# MS20_schematic.net
KiCad netlist of a schematic drawn in Altium Designer
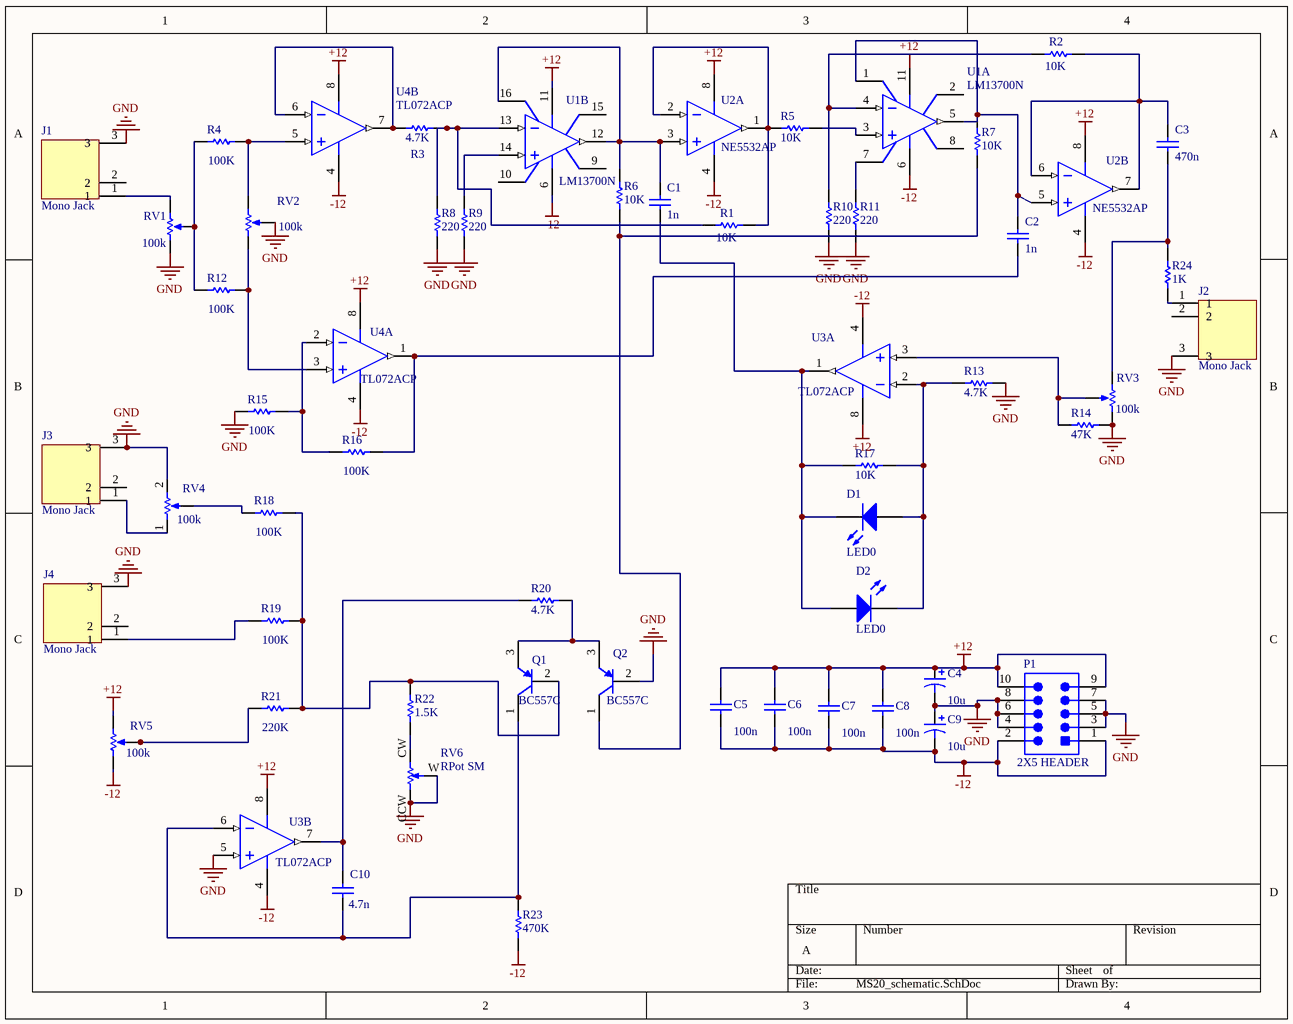
[diagram p0: MS20_schematic.SchDoc]

(export (version "E")
  (design (tool "Eeschema 10.0.6"))
  (components
    (comp (ref "C1")
      (value "1n")
      (footprint "RAD-0.3")
      (description "Capacitor")
      (fields (field (name "Comment") "Cap") (field (name "PUBLISHER") "Altium Limited"))
      (libsource (lib "Miscellaneous Devices") (part "Cap"))
    )
    (comp (ref "C2")
      (value "1n")
      (footprint "RAD-0.3")
      (description "Capacitor")
      (fields (field (name "Comment") "Cap") (field (name "PUBLISHER") "Altium Limited"))
      (libsource (lib "Miscellaneous Devices") (part "Cap"))
    )
    (comp (ref "C3")
      (value "470n")
      (footprint "RAD-0.3")
      (description "Capacitor")
      (fields (field (name "Comment") "Cap") (field (name "PUBLISHER") "Altium Limited"))
      (libsource (lib "Miscellaneous Devices") (part "Cap"))
    )
    (comp (ref "C4")
      (value "10u")
      (footprint "RB7.6-15")
      (description "Polarized Capacitor (Radial)")
      (fields (field (name "Comment") "Cap Pol1") (field (name "PUBLISHER") "Altium Limited"))
      (libsource (lib "Miscellaneous Devices") (part "Cap Pol1"))
    )
    (comp (ref "C5")
      (value "100n")
      (footprint "RAD-0.3")
      (description "Capacitor")
      (fields (field (name "Comment") "Cap") (field (name "PUBLISHER") "Altium Limited"))
      (libsource (lib "Miscellaneous Devices") (part "Cap"))
    )
    (comp (ref "C6")
      (value "100n")
      (footprint "RAD-0.3")
      (description "Capacitor")
      (fields (field (name "Comment") "Cap") (field (name "PUBLISHER") "Altium Limited"))
      (libsource (lib "Miscellaneous Devices") (part "Cap"))
    )
    (comp (ref "C7")
      (value "100n")
      (footprint "RAD-0.3")
      (description "Capacitor")
      (fields (field (name "Comment") "Cap") (field (name "PUBLISHER") "Altium Limited"))
      (libsource (lib "Miscellaneous Devices") (part "Cap"))
    )
    (comp (ref "C8")
      (value "100n")
      (footprint "RAD-0.3")
      (description "Capacitor")
      (fields (field (name "Comment") "Cap") (field (name "PUBLISHER") "Altium Limited"))
      (libsource (lib "Miscellaneous Devices") (part "Cap"))
    )
    (comp (ref "C9")
      (value "10u")
      (footprint "RB7.6-15")
      (description "Polarized Capacitor (Radial)")
      (fields (field (name "Comment") "Cap Pol1") (field (name "PUBLISHER") "Altium Limited"))
      (libsource (lib "Miscellaneous Devices") (part "Cap Pol1"))
    )
    (comp (ref "C10")
      (value "4.7n")
      (footprint "RAD-0.3")
      (description "Capacitor")
      (fields (field (name "Comment") "Cap") (field (name "PUBLISHER") "Altium Limited"))
      (libsource (lib "Miscellaneous Devices") (part "Cap"))
    )
    (comp (ref "D1")
      (value "LED0")
      (footprint "LED-0")
      (description "Typical INFRARED GaAs LED")
      (fields (field (name "PUBLISHER") "Altium Limited"))
      (libsource (lib "Miscellaneous Devices") (part "LED0"))
    )
    (comp (ref "D2")
      (value "LED0")
      (footprint "LED-0")
      (description "Typical INFRARED GaAs LED")
      (fields (field (name "PUBLISHER") "Altium Limited"))
      (libsource (lib "Miscellaneous Devices") (part "LED0"))
    )
    (comp (ref "J1")
      (value "Mono Jack")
      (footprint "MONO_Jack")
      (description "Phone Connectors Audio Socket 3.5MM 2P SCR")
      (fields (field (name "MANUFACTURER") "Schurter") (field (name "MANUFACTURER PART NUMBER") "4832.2211"))
      (libsource (lib "") (part "4832.2211_1"))
    )
    (comp (ref "J2")
      (value "Mono Jack")
      (footprint "MONO_Jack")
      (description "Phone Connectors Audio Socket 3.5MM 2P SCR")
      (fields (field (name "MANUFACTURER") "Schurter") (field (name "MANUFACTURER PART NUMBER") "4832.2211"))
      (libsource (lib "Schlib1") (part "4832.2211"))
    )
    (comp (ref "J3")
      (value "Mono Jack")
      (footprint "MONO_Jack")
      (description "Phone Connectors Audio Socket 3.5MM 2P SCR")
      (fields (field (name "MANUFACTURER") "Schurter") (field (name "MANUFACTURER PART NUMBER") "4832.2211"))
      (libsource (lib "") (part "4832.2211_1"))
    )
    (comp (ref "J4")
      (value "Mono Jack")
      (footprint "MONO_Jack")
      (description "Phone Connectors Audio Socket 3.5MM 2P SCR")
      (fields (field (name "MANUFACTURER") "Schurter") (field (name "MANUFACTURER PART NUMBER") "4832.2211"))
      (libsource (lib "") (part "4832.2211_1"))
    )
    (comp (ref "P1")
      (value "2X5 HEADER")
      (footprint "TECO-1-1634688-0-10_V")
      (fields (field (name "MANUFACTURER") "TE Connectivity") (field (name "PARTNUMBER") "1-1634688-0"))
      (libsource (lib "Altium Content Vault") (part "CN-2P-M-R10"))
    )
    (comp (ref "Q1")
      (value "BC557C")
      (footprint "ONSC-TO-92-3-29-11")
      (description "Amplifier Transistor, PNP Silicon, 3-Pin TO-92, Bulk Box")
      (fields (field (name "MANUFACTURER") "On Semiconductor"))
      (libsource (lib "Altium Content Vault") (part "ONSC-PNP-C1B2E3-3"))
    )
    (comp (ref "Q2")
      (value "BC557C")
      (footprint "ONSC-TO-92-3-29-11")
      (description "Amplifier Transistor, PNP Silicon, 3-Pin TO-92, Bulk Box")
      (fields (field (name "MANUFACTURER") "On Semiconductor"))
      (libsource (lib "Altium Content Vault") (part "ONSC-PNP-C1B2E3-3"))
    )
    (comp (ref "R1")
      (value "10K")
      (footprint "AXIAL-0.3")
      (description "Resistor")
      (fields (field (name "Comment") "Res1") (field (name "PUBLISHER") "Altium Limited"))
      (libsource (lib "Miscellaneous Devices") (part "Res1"))
    )
    (comp (ref "R2")
      (value "10K")
      (footprint "AXIAL-0.3")
      (description "Resistor")
      (fields (field (name "Comment") "Res1") (field (name "PUBLISHER") "Altium Limited"))
      (libsource (lib "Miscellaneous Devices") (part "Res1"))
    )
    (comp (ref "R3")
      (value "4.7K")
      (footprint "AXIAL-0.3")
      (description "Resistor")
      (fields (field (name "Comment") "Res1") (field (name "PUBLISHER") "Altium Limited"))
      (libsource (lib "Miscellaneous Devices") (part "Res1"))
    )
    (comp (ref "R4")
      (value "100K")
      (footprint "AXIAL-0.3")
      (description "Resistor")
      (fields (field (name "Comment") "Res1") (field (name "PUBLISHER") "Altium Limited"))
      (libsource (lib "Miscellaneous Devices") (part "Res1"))
    )
    (comp (ref "R5")
      (value "10K")
      (footprint "AXIAL-0.3")
      (description "Resistor")
      (fields (field (name "Comment") "Res1") (field (name "PUBLISHER") "Altium Limited"))
      (libsource (lib "Miscellaneous Devices") (part "Res1"))
    )
    (comp (ref "R6")
      (value "10K")
      (footprint "AXIAL-0.3")
      (description "Resistor")
      (fields (field (name "Comment") "Res1") (field (name "PUBLISHER") "Altium Limited"))
      (libsource (lib "Miscellaneous Devices") (part "Res1"))
    )
    (comp (ref "R7")
      (value "10K")
      (footprint "AXIAL-0.3")
      (description "Resistor")
      (fields (field (name "Comment") "Res1") (field (name "PUBLISHER") "Altium Limited"))
      (libsource (lib "Miscellaneous Devices") (part "Res1"))
    )
    (comp (ref "R8")
      (value "220")
      (footprint "AXIAL-0.3")
      (description "Resistor")
      (fields (field (name "Comment") "Res1") (field (name "PUBLISHER") "Altium Limited"))
      (libsource (lib "Miscellaneous Devices") (part "Res1"))
    )
    (comp (ref "R9")
      (value "220")
      (footprint "AXIAL-0.3")
      (description "Resistor")
      (fields (field (name "Comment") "Res1") (field (name "PUBLISHER") "Altium Limited"))
      (libsource (lib "Miscellaneous Devices") (part "Res1"))
    )
    (comp (ref "R10")
      (value "220")
      (footprint "AXIAL-0.3")
      (description "Resistor")
      (fields (field (name "Comment") "Res1") (field (name "PUBLISHER") "Altium Limited"))
      (libsource (lib "Miscellaneous Devices") (part "Res1"))
    )
    (comp (ref "R11")
      (value "220")
      (footprint "AXIAL-0.3")
      (description "Resistor")
      (fields (field (name "Comment") "Res1") (field (name "PUBLISHER") "Altium Limited"))
      (libsource (lib "Miscellaneous Devices") (part "Res1"))
    )
    (comp (ref "R12")
      (value "100K")
      (footprint "AXIAL-0.3")
      (description "Resistor")
      (fields (field (name "Comment") "Res1") (field (name "PUBLISHER") "Altium Limited"))
      (libsource (lib "Miscellaneous Devices") (part "Res1"))
    )
    (comp (ref "R13")
      (value "4.7K")
      (footprint "AXIAL-0.3")
      (description "Resistor")
      (fields (field (name "Comment") "Res1") (field (name "PUBLISHER") "Altium Limited"))
      (libsource (lib "Miscellaneous Devices") (part "Res1"))
    )
    (comp (ref "R14")
      (value "47K")
      (footprint "AXIAL-0.3")
      (description "Resistor")
      (fields (field (name "Comment") "Res1") (field (name "PUBLISHER") "Altium Limited"))
      (libsource (lib "Miscellaneous Devices") (part "Res1"))
    )
    (comp (ref "R15")
      (value "100K")
      (footprint "AXIAL-0.3")
      (description "Resistor")
      (fields (field (name "Comment") "Res1") (field (name "PUBLISHER") "Altium Limited"))
      (libsource (lib "Miscellaneous Devices") (part "Res1"))
    )
    (comp (ref "R16")
      (value "100K")
      (footprint "AXIAL-0.3")
      (description "Resistor")
      (fields (field (name "Comment") "Res1") (field (name "PUBLISHER") "Altium Limited"))
      (libsource (lib "Miscellaneous Devices") (part "Res1"))
    )
    (comp (ref "R17")
      (value "10K")
      (footprint "AXIAL-0.3")
      (description "Resistor")
      (fields (field (name "Comment") "Res1") (field (name "PUBLISHER") "Altium Limited"))
      (libsource (lib "Miscellaneous Devices") (part "Res1"))
    )
    (comp (ref "R18")
      (value "100K")
      (footprint "AXIAL-0.3")
      (description "Resistor")
      (fields (field (name "Comment") "Res1") (field (name "PUBLISHER") "Altium Limited"))
      (libsource (lib "Miscellaneous Devices") (part "Res1"))
    )
    (comp (ref "R19")
      (value "100K")
      (footprint "AXIAL-0.3")
      (description "Resistor")
      (fields (field (name "Comment") "Res1") (field (name "PUBLISHER") "Altium Limited"))
      (libsource (lib "Miscellaneous Devices") (part "Res1"))
    )
    (comp (ref "R20")
      (value "4.7K")
      (footprint "AXIAL-0.3")
      (description "Resistor")
      (fields (field (name "Comment") "Res1") (field (name "PUBLISHER") "Altium Limited"))
      (libsource (lib "Miscellaneous Devices") (part "Res1"))
    )
    (comp (ref "R21")
      (value "220K")
      (footprint "AXIAL-0.3")
      (description "Resistor")
      (fields (field (name "Comment") "Res1") (field (name "PUBLISHER") "Altium Limited"))
      (libsource (lib "Miscellaneous Devices") (part "Res1"))
    )
    (comp (ref "R22")
      (value "1.5K")
      (footprint "AXIAL-0.3")
      (description "Resistor")
      (fields (field (name "Comment") "Res1") (field (name "PUBLISHER") "Altium Limited"))
      (libsource (lib "Miscellaneous Devices") (part "Res1"))
    )
    (comp (ref "R23")
      (value "470K")
      (footprint "AXIAL-0.3")
      (description "Resistor")
      (fields (field (name "Comment") "Res1") (field (name "PUBLISHER") "Altium Limited"))
      (libsource (lib "Miscellaneous Devices") (part "Res1"))
    )
    (comp (ref "R24")
      (value "1K")
      (footprint "AXIAL-0.3")
      (description "Resistor")
      (fields (field (name "Comment") "Res1") (field (name "PUBLISHER") "Altium Limited"))
      (libsource (lib "Miscellaneous Devices") (part "Res1"))
    )
    (comp (ref "RV1")
      (value "100k")
      (footprint "VR5")
      (description "Potentiometer")
      (fields (field (name "Comment") "RPot") (field (name "PUBLISHER") "Altium Limited"))
      (libsource (lib "Miscellaneous Devices") (part "RPot"))
    )
    (comp (ref "RV2")
      (value "100k")
      (footprint "VR5")
      (description "Potentiometer")
      (fields (field (name "Comment") "RPot") (field (name "PUBLISHER") "Altium Limited"))
      (libsource (lib "Miscellaneous Devices") (part "RPot"))
    )
    (comp (ref "RV3")
      (value "100k")
      (footprint "VR5")
      (description "Potentiometer")
      (fields (field (name "Comment") "RPot") (field (name "PUBLISHER") "Altium Limited"))
      (libsource (lib "Miscellaneous Devices") (part "RPot"))
    )
    (comp (ref "RV4")
      (value "100k")
      (footprint "VR5")
      (description "Potentiometer")
      (fields (field (name "Comment") "RPot") (field (name "PUBLISHER") "Altium Limited"))
      (libsource (lib "") (part "RPot_1"))
    )
    (comp (ref "RV5")
      (value "100k")
      (footprint "VR5")
      (description "Potentiometer")
      (fields (field (name "Comment") "RPot") (field (name "PUBLISHER") "Altium Limited"))
      (libsource (lib "Miscellaneous Devices") (part "RPot"))
    )
    (comp (ref "RV6")
      (value "RPot SM")
      (footprint "POT4MM-2")
      (description "Square Trimming Potentiometer")
      (fields (field (name "PUBLISHER") "Altium Limited"))
      (libsource (lib "Miscellaneous Devices") (part "RPot SM"))
    )
    (comp (ref "U1")
      (value "LM13700N")
      (footprint "NFG0016A")
      (description "Dual Operational Transconductance Amplifier with Linearizing Diodes and Buffers, 16-pin MDIP")
      (fields (field (name "MANUFACTURER") "Texas Instruments"))
      (libsource (lib "Altium Content Vault") (part "AMP-TRCA-LM13700-16"))
    )
    (comp (ref "U2")
      (value "NE5532AP")
      (footprint "P0008A")
      (description "Dual Low-Noise Operational Amplifier, 10 to 30 V, 0 to 70 degC, 8-pin DIP (P8), Pb-Free (RoHS)")
      (fields (field (name "MANUFACTURER") "Texas Instruments"))
      (libsource (lib "Altium Content Vault") (part "TI-AMP-D6-2-8_D"))
    )
    (comp (ref "U3")
      (value "TL072ACP")
      (footprint "P0008A")
      (fields (field (name "MANUFACTURER") "Texas Instruments"))
      (libsource (lib "Altium Content Vault") (part "TI-AMP-D6-2-8_D"))
    )
    (comp (ref "U4")
      (value "TL072ACP")
      (footprint "P0008A")
      (fields (field (name "MANUFACTURER") "Texas Instruments"))
      (libsource (lib "Altium Content Vault") (part "TI-AMP-D6-2-8_D"))
    )
  )
  (nets
    (net (code "1") (name "+12") (class "Default")
      (node (ref "C4") (pin "1") (pinfunction "1_1") (pintype "passive"))
      (node (ref "C5") (pin "1") (pinfunction "1_1") (pintype "passive"))
      (node (ref "C6") (pin "1") (pinfunction "1_1") (pintype "passive"))
      (node (ref "C7") (pin "1") (pinfunction "1_1") (pintype "passive"))
      (node (ref "C8") (pin "1") (pinfunction "1_1") (pintype "passive"))
      (node (ref "P1") (pin "10") (pinfunction "10_10") (pintype "passive"))
      (node (ref "P1") (pin "9") (pinfunction "9_9") (pintype "passive"))
      (node (ref "RV5") (pin "2") (pinfunction "BOT_2") (pintype "passive"))
      (node (ref "U1") (pin "11") (pinfunction "V+_11") (pintype "power_in"))
      (node (ref "U2") (pin "8") (pinfunction "VCC+_8") (pintype "power_in"))
      (node (ref "U3") (pin "8") (pinfunction "VCC+_8") (pintype "power_in"))
      (node (ref "U4") (pin "8") (pinfunction "VCC+_8") (pintype "power_in"))
    )
    (net (code "2") (name "-12") (class "Default")
      (node (ref "C5") (pin "2") (pinfunction "2_2") (pintype "passive"))
      (node (ref "C6") (pin "2") (pinfunction "2_2") (pintype "passive"))
      (node (ref "C7") (pin "2") (pinfunction "2_2") (pintype "passive"))
      (node (ref "C8") (pin "2") (pinfunction "2_2") (pintype "passive"))
      (node (ref "C9") (pin "2") (pinfunction "2_2") (pintype "passive"))
      (node (ref "P1") (pin "1") (pinfunction "1_1") (pintype "passive"))
      (node (ref "P1") (pin "2") (pinfunction "2_2") (pintype "passive"))
      (node (ref "R23") (pin "2") (pinfunction "2_2") (pintype "passive"))
      (node (ref "RV5") (pin "1") (pinfunction "TOP_1") (pintype "passive"))
      (node (ref "U1") (pin "6") (pinfunction "V-_6") (pintype "power_in"))
      (node (ref "U2") (pin "4") (pinfunction "VCC-_4") (pintype "power_in"))
      (node (ref "U3") (pin "4") (pinfunction "VCC-_4") (pintype "power_in"))
      (node (ref "U4") (pin "4") (pinfunction "VCC-_4") (pintype "power_in"))
    )
    (net (code "3") (name "GND") (class "Default")
      (node (ref "C4") (pin "2") (pinfunction "2_2") (pintype "passive"))
      (node (ref "C9") (pin "1") (pinfunction "1_1") (pintype "passive"))
      (node (ref "J1") (pin "3") (pinfunction "3_3") (pintype "passive"))
      (node (ref "J2") (pin "3") (pinfunction "3_3") (pintype "passive"))
      (node (ref "J3") (pin "3") (pinfunction "3_3") (pintype "passive"))
      (node (ref "J4") (pin "3") (pinfunction "3_3") (pintype "passive"))
      (node (ref "P1") (pin "3") (pinfunction "3_3") (pintype "passive"))
      (node (ref "P1") (pin "4") (pinfunction "4_4") (pintype "passive"))
      (node (ref "P1") (pin "5") (pinfunction "5_5") (pintype "passive"))
      (node (ref "P1") (pin "6") (pinfunction "6_6") (pintype "passive"))
      (node (ref "P1") (pin "7") (pinfunction "7_7") (pintype "passive"))
      (node (ref "P1") (pin "8") (pinfunction "8_8") (pintype "passive"))
      (node (ref "Q2") (pin "2") (pinfunction "B_2") (pintype "passive"))
      (node (ref "R10") (pin "1") (pinfunction "1_1") (pintype "passive"))
      (node (ref "R11") (pin "1") (pinfunction "1_1") (pintype "passive"))
      (node (ref "R13") (pin "1") (pinfunction "1_1") (pintype "passive"))
      (node (ref "R14") (pin "1") (pinfunction "1_1") (pintype "passive"))
      (node (ref "R15") (pin "1") (pinfunction "1_1") (pintype "passive"))
      (node (ref "R8") (pin "1") (pinfunction "1_1") (pintype "passive"))
      (node (ref "R9") (pin "1") (pinfunction "1_1") (pintype "passive"))
      (node (ref "RV1") (pin "1") (pinfunction "TOP_1") (pintype "passive"))
      (node (ref "RV2") (pin "3") (pinfunction "TAP_3") (pintype "passive"))
      (node (ref "RV3") (pin "2") (pinfunction "BOT_2") (pintype "passive"))
      (node (ref "RV4") (pin "2") (pinfunction "BOT_2") (pintype "passive"))
      (node (ref "RV6") (pin "CCW") (pinfunction "-_CCW") (pintype "passive"))
      (node (ref "RV6") (pin "W") (pinfunction "W_W") (pintype "passive"))
      (node (ref "U3") (pin "5") (pinfunction "IN2+_5") (pintype "input"))
    )
    (net (code "4") (name "Net-(D1-A)") (class "Default")
      (node (ref "D1") (pin "1") (pinfunction "A_1") (pintype "passive"))
      (node (ref "D2") (pin "2") (pinfunction "K_2") (pintype "passive"))
      (node (ref "R13") (pin "2") (pinfunction "2_2") (pintype "passive"))
      (node (ref "R17") (pin "1") (pinfunction "1_1") (pintype "passive"))
      (node (ref "U3") (pin "2") (pinfunction "IN1-_2") (pintype "input"))
    )
    (net (code "5") (name "Net-(D1-K)") (class "Default")
      (node (ref "C1") (pin "2") (pinfunction "2_2") (pintype "passive"))
      (node (ref "D1") (pin "2") (pinfunction "K_2") (pintype "passive"))
      (node (ref "D2") (pin "1") (pinfunction "A_1") (pintype "passive"))
      (node (ref "R17") (pin "2") (pinfunction "2_2") (pintype "passive"))
      (node (ref "U3") (pin "1") (pinfunction "OUT1_1") (pintype "output"))
    )
    (net (code "6") (name "Net-(J2-Pad1)") (class "Default")
      (node (ref "J2") (pin "1") (pinfunction "1_1") (pintype "passive"))
      (node (ref "R24") (pin "1") (pinfunction "1_1") (pintype "passive"))
    )
    (net (code "7") (name "Net-(J4-Pad1)") (class "Default")
      (node (ref "J4") (pin "1") (pinfunction "1_1") (pintype "passive"))
      (node (ref "R19") (pin "1") (pinfunction "1_1") (pintype "passive"))
    )
    (net (code "8") (name "Net-(Q1-B)") (class "Default")
      (node (ref "Q1") (pin "2") (pinfunction "B_2") (pintype "passive"))
      (node (ref "R18") (pin "2") (pinfunction "2_2") (pintype "passive"))
      (node (ref "R19") (pin "2") (pinfunction "2_2") (pintype "passive"))
      (node (ref "R21") (pin "2") (pinfunction "2_2") (pintype "passive"))
      (node (ref "R22") (pin "2") (pinfunction "2_2") (pintype "passive"))
    )
    (net (code "9") (name "Net-(Q1-C)") (class "Default")
      (node (ref "C10") (pin "2") (pinfunction "2_2") (pintype "passive"))
      (node (ref "Q1") (pin "1") (pinfunction "C_1") (pintype "passive"))
      (node (ref "R23") (pin "1") (pinfunction "1_1") (pintype "passive"))
      (node (ref "U3") (pin "6") (pinfunction "IN2-_6") (pintype "input"))
    )
    (net (code "10") (name "Net-(Q1-E)") (class "Default")
      (node (ref "Q1") (pin "3") (pinfunction "E_3") (pintype "passive"))
      (node (ref "Q2") (pin "3") (pinfunction "E_3") (pintype "passive"))
      (node (ref "R20") (pin "1") (pinfunction "1_1") (pintype "passive"))
    )
    (net (code "11") (name "Net-(Q2-C)") (class "Default")
      (node (ref "Q2") (pin "1") (pinfunction "C_1") (pintype "passive"))
      (node (ref "R6") (pin "1") (pinfunction "1_1") (pintype "passive"))
      (node (ref "R7") (pin "1") (pinfunction "1_1") (pintype "passive"))
    )
    (net (code "12") (name "Net-(RV1-BOT)") (class "Default")
      (node (ref "J1") (pin "1") (pinfunction "1_1") (pintype "passive"))
      (node (ref "RV1") (pin "2") (pinfunction "BOT_2") (pintype "passive"))
    )
    (net (code "13") (name "Net-(RV1-TAP)") (class "Default")
      (node (ref "R12") (pin "1") (pinfunction "1_1") (pintype "passive"))
      (node (ref "R4") (pin "1") (pinfunction "1_1") (pintype "passive"))
      (node (ref "RV1") (pin "3") (pinfunction "TAP_3") (pintype "passive"))
    )
    (net (code "14") (name "Net-(RV2-BOT)") (class "Default")
      (node (ref "R4") (pin "2") (pinfunction "2_2") (pintype "passive"))
      (node (ref "RV2") (pin "2") (pinfunction "BOT_2") (pintype "passive"))
      (node (ref "U4") (pin "5") (pinfunction "IN2+_5") (pintype "input"))
    )
    (net (code "15") (name "Net-(RV2-TOP)") (class "Default")
      (node (ref "R12") (pin "2") (pinfunction "2_2") (pintype "passive"))
      (node (ref "RV2") (pin "1") (pinfunction "TOP_1") (pintype "passive"))
      (node (ref "U4") (pin "3") (pinfunction "IN1+_3") (pintype "input"))
    )
    (net (code "16") (name "Net-(RV3-TAP)") (class "Default")
      (node (ref "R14") (pin "2") (pinfunction "2_2") (pintype "passive"))
      (node (ref "RV3") (pin "3") (pinfunction "TAP_3") (pintype "passive"))
      (node (ref "U3") (pin "3") (pinfunction "IN1+_3") (pintype "input"))
    )
    (net (code "17") (name "Net-(RV3-TOP)") (class "Default")
      (node (ref "C3") (pin "2") (pinfunction "2_2") (pintype "passive"))
      (node (ref "R24") (pin "2") (pinfunction "2_2") (pintype "passive"))
      (node (ref "RV3") (pin "1") (pinfunction "TOP_1") (pintype "passive"))
    )
    (net (code "18") (name "Net-(RV4-TAP)") (class "Default")
      (node (ref "R18") (pin "1") (pinfunction "1_1") (pintype "passive"))
      (node (ref "RV4") (pin "3") (pinfunction "TAP_3") (pintype "passive"))
    )
    (net (code "19") (name "Net-(RV4-TOP)") (class "Default")
      (node (ref "J3") (pin "1") (pinfunction "1_1") (pintype "passive"))
      (node (ref "RV4") (pin "1") (pinfunction "TOP_1") (pintype "passive"))
    )
    (net (code "20") (name "Net-(RV5-TAP)") (class "Default")
      (node (ref "R21") (pin "1") (pinfunction "1_1") (pintype "passive"))
      (node (ref "RV5") (pin "3") (pinfunction "TAP_3") (pintype "passive"))
    )
    (net (code "21") (name "Net-(RV6-+)") (class "Default")
      (node (ref "R22") (pin "1") (pinfunction "1_1") (pintype "passive"))
      (node (ref "RV6") (pin "CW") (pinfunction "+_CW") (pintype "passive"))
    )
    (net (code "22") (name "Net-(U1A-AMP_BIAS_IN1)") (class "Default")
      (node (ref "C2") (pin "1") (pinfunction "1_1") (pintype "passive"))
      (node (ref "R7") (pin "2") (pinfunction "2_2") (pintype "passive"))
      (node (ref "U1") (pin "1") (pinfunction "AMP_BIAS_IN1_1") (pintype "passive"))
      (node (ref "U1") (pin "5") (pinfunction "OUT1_5") (pintype "output"))
      (node (ref "U2") (pin "5") (pinfunction "IN2+_5") (pintype "input"))
    )
    (net (code "23") (name "Net-(U1A-BUF_IN1)") (class "Default")
      (node (ref "R11") (pin "2") (pinfunction "2_2") (pintype "passive"))
      (node (ref "U1") (pin "7") (pinfunction "BUF_IN1_7") (pintype "passive"))
    )
    (net (code "24") (name "Net-(U1A-IN1+)") (class "Default")
      (node (ref "R5") (pin "1") (pinfunction "1_1") (pintype "passive"))
      (node (ref "U1") (pin "3") (pinfunction "IN1+_3") (pintype "input"))
    )
    (net (code "25") (name "Net-(U1A-IN1-)") (class "Default")
      (node (ref "R10") (pin "2") (pinfunction "2_2") (pintype "passive"))
      (node (ref "R2") (pin "2") (pinfunction "2_2") (pintype "passive"))
      (node (ref "U1") (pin "4") (pinfunction "IN1-_4") (pintype "input"))
    )
    (net (code "26") (name "Net-(U1B-AMP_BIAS_IN2)") (class "Default")
      (node (ref "C1") (pin "1") (pinfunction "1_1") (pintype "passive"))
      (node (ref "R6") (pin "2") (pinfunction "2_2") (pintype "passive"))
      (node (ref "U1") (pin "12") (pinfunction "OUT2_12") (pintype "output"))
      (node (ref "U1") (pin "16") (pinfunction "AMP_BIAS_IN2_16") (pintype "passive"))
      (node (ref "U2") (pin "3") (pinfunction "IN1+_3") (pintype "input"))
    )
    (net (code "27") (name "Net-(U1B-IN2+)") (class "Default")
      (node (ref "R9") (pin "2") (pinfunction "2_2") (pintype "passive"))
      (node (ref "U1") (pin "14") (pinfunction "IN2+_14") (pintype "input"))
    )
    (net (code "28") (name "Net-(U1B-IN2-)") (class "Default")
      (node (ref "R1") (pin "2") (pinfunction "2_2") (pintype "passive"))
      (node (ref "R3") (pin "1") (pinfunction "1_1") (pintype "passive"))
      (node (ref "R8") (pin "2") (pinfunction "2_2") (pintype "passive"))
      (node (ref "U1") (pin "13") (pinfunction "IN2-_13") (pintype "input"))
    )
    (net (code "29") (name "Net-(U2A-IN1-)") (class "Default")
      (node (ref "R1") (pin "1") (pinfunction "1_1") (pintype "passive"))
      (node (ref "R5") (pin "2") (pinfunction "2_2") (pintype "passive"))
      (node (ref "U2") (pin "1") (pinfunction "OUT1_1") (pintype "output"))
      (node (ref "U2") (pin "2") (pinfunction "IN1-_2") (pintype "input"))
    )
    (net (code "30") (name "Net-(U2B-IN2-)") (class "Default")
      (node (ref "C3") (pin "1") (pinfunction "1_1") (pintype "passive"))
      (node (ref "R2") (pin "1") (pinfunction "1_1") (pintype "passive"))
      (node (ref "U2") (pin "6") (pinfunction "IN2-_6") (pintype "input"))
      (node (ref "U2") (pin "7") (pinfunction "OUT2_7") (pintype "output"))
    )
    (net (code "31") (name "Net-(U3B-OUT2)") (class "Default")
      (node (ref "C10") (pin "1") (pinfunction "1_1") (pintype "passive"))
      (node (ref "R20") (pin "2") (pinfunction "2_2") (pintype "passive"))
      (node (ref "U3") (pin "7") (pinfunction "OUT2_7") (pintype "output"))
    )
    (net (code "32") (name "Net-(U4A-IN1-)") (class "Default")
      (node (ref "R15") (pin "2") (pinfunction "2_2") (pintype "passive"))
      (node (ref "R16") (pin "1") (pinfunction "1_1") (pintype "passive"))
      (node (ref "U4") (pin "2") (pinfunction "IN1-_2") (pintype "input"))
    )
    (net (code "33") (name "Net-(U4A-OUT1)") (class "Default")
      (node (ref "C2") (pin "2") (pinfunction "2_2") (pintype "passive"))
      (node (ref "R16") (pin "2") (pinfunction "2_2") (pintype "passive"))
      (node (ref "U4") (pin "1") (pinfunction "OUT1_1") (pintype "output"))
    )
    (net (code "34") (name "Net-(U4B-IN2-)") (class "Default")
      (node (ref "R3") (pin "2") (pinfunction "2_2") (pintype "passive"))
      (node (ref "U4") (pin "6") (pinfunction "IN2-_6") (pintype "input"))
      (node (ref "U4") (pin "7") (pinfunction "OUT2_7") (pintype "output"))
    )
    (net (code "35") (name "unconnected-(J1-Pad2)") (class "Default")
      (node (ref "J1") (pin "2") (pinfunction "2_2") (pintype "passive"))
    )
    (net (code "36") (name "unconnected-(J2-Pad2)") (class "Default")
      (node (ref "J2") (pin "2") (pinfunction "2_2") (pintype "passive"))
    )
    (net (code "37") (name "unconnected-(J3-Pad2)") (class "Default")
      (node (ref "J3") (pin "2") (pinfunction "2_2") (pintype "passive"))
    )
    (net (code "38") (name "unconnected-(J4-Pad2)") (class "Default")
      (node (ref "J4") (pin "2") (pinfunction "2_2") (pintype "passive"))
    )
    (net (code "39") (name "unconnected-(U1A-BUF_OUT1-Pad8)") (class "Default")
      (node (ref "U1") (pin "8") (pinfunction "BUF_OUT1_8") (pintype "passive"))
    )
    (net (code "40") (name "unconnected-(U1A-DIODE_BIAS1-Pad2)") (class "Default")
      (node (ref "U1") (pin "2") (pinfunction "DIODE_BIAS1_2") (pintype "passive"))
    )
    (net (code "41") (name "unconnected-(U1B-BUF_IN2-Pad10)") (class "Default")
      (node (ref "U1") (pin "10") (pinfunction "BUF_IN2_10") (pintype "passive"))
    )
    (net (code "42") (name "unconnected-(U1B-BUF_OUT2-Pad9)") (class "Default")
      (node (ref "U1") (pin "9") (pinfunction "BUF_OUT2_9") (pintype "passive"))
    )
    (net (code "43") (name "unconnected-(U1B-DIODE_BIAS2-Pad15)") (class "Default")
      (node (ref "U1") (pin "15") (pinfunction "DIODE_BIAS2_15") (pintype "passive"))
    )
  )
)
